# CCR2.net
KiCad netlist of a schematic drawn in EAGLE
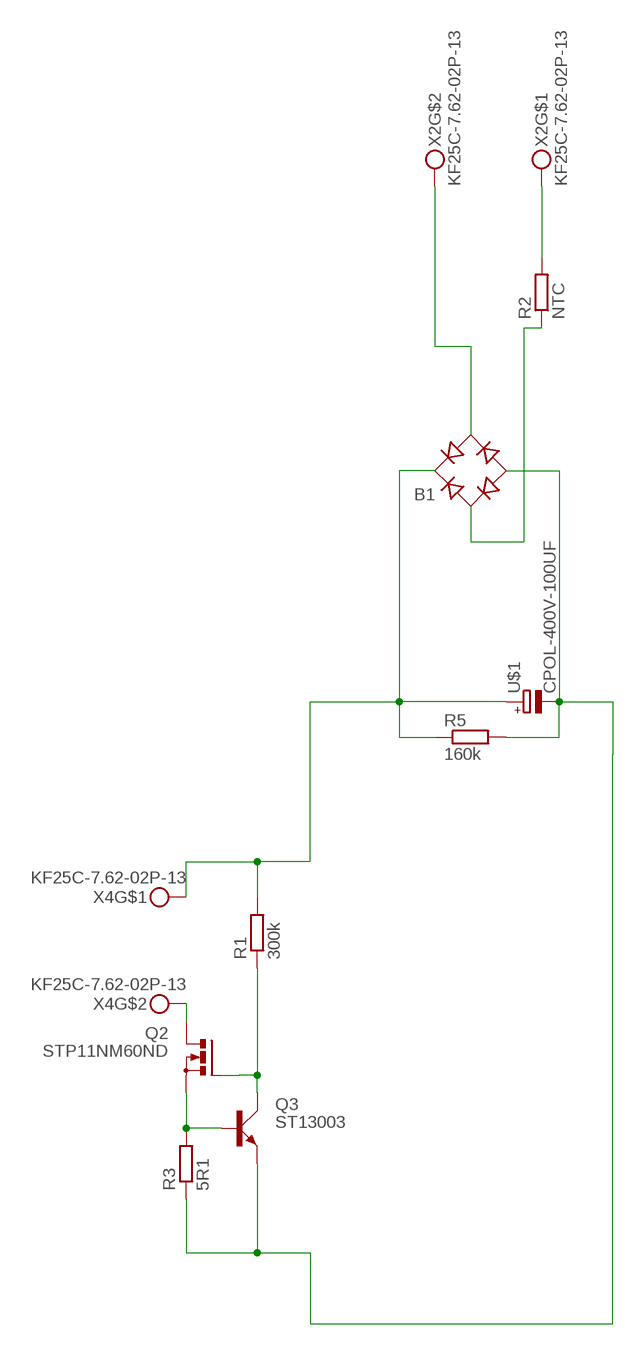
[diagram p0: schematic, sheet 1]

(export (version "E")
  (design (tool "Eeschema 10.0.6"))
  (components
    (comp (ref "B1")
      (value "RB1A")
      (footprint "eagle-import:RB1A")
      (libsource (lib "eagle-import") (part "RB1A"))
    )
    (comp (ref "Q2")
      (value "STP11NM60ND")
      (footprint "eagle-import:TO220BV")
      (libsource (lib "eagle-import") (part "BUZ11BV"))
    )
    (comp (ref "Q3")
      (value "ST13003")
      (footprint "eagle-import:SOT-92WIDE")
      (libsource (lib "eagle-import") (part "KSP42TA"))
    )
    (comp (ref "R1")
      (value "300k")
      (footprint "eagle-import:0411_12")
      (libsource (lib "eagle-import") (part "R-EU_0411/12"))
    )
    (comp (ref "R2")
      (value "NTC")
      (footprint "eagle-import:0309_10")
      (libsource (lib "eagle-import") (part "R-EU_0309/10"))
    )
    (comp (ref "R3")
      (value "5R1")
      (footprint "eagle-import:R0805")
      (libsource (lib "eagle-import") (part "R-EU_R0805"))
    )
    (comp (ref "R5")
      (value "160k")
      (footprint "eagle-import:0204_7")
      (libsource (lib "eagle-import") (part "R-EU_0204/7"))
    )
    (comp (ref "U$1")
      (value "CPOL-400V-100UF")
      (footprint "eagle-import:18_36.5_7.62")
      (libsource (lib "eagle-import") (part "CPOL-400V-100UF"))
    )
    (comp (ref "X2")
      (value "KF25C-7.62-02P-13")
      (footprint "eagle-import:KF25C-7.62-02P-13")
      (libsource (lib "eagle-import") (part "KF25C-7.62-02P-13"))
    )
    (comp (ref "X4")
      (value "KF25C-7.62-02P-13")
      (footprint "eagle-import:KF25C-7.62-02P-13")
      (libsource (lib "eagle-import") (part "KF25C-7.62-02P-13"))
    )
  )
  (nets
    (net (code "1") (name "Net-(B1-PadAC1)") (class "Default")
      (node (ref "B1") (pin "AC1") (pinfunction "AC1_AC1") (pintype "passive"))
      (node (ref "R2") (pin "1") (pinfunction "1_1") (pintype "passive"))
    )
    (net (code "2") (name "Net-(Q2-PadG)") (class "Default")
      (node (ref "Q2") (pin "G") (pinfunction "G_G") (pintype "passive"))
      (node (ref "Q3") (pin "C") (pinfunction "C_C") (pintype "passive"))
      (node (ref "R1") (pin "1") (pinfunction "1_1") (pintype "passive"))
    )
    (net (code "3") (name "Net-(Q2-PadS)") (class "Default")
      (node (ref "Q2") (pin "S") (pinfunction "S_S") (pintype "passive"))
      (node (ref "Q3") (pin "B") (pinfunction "B_B") (pintype "passive"))
      (node (ref "R3") (pin "2") (pinfunction "2_2") (pintype "passive"))
    )
    (net (code "4") (name "Net-(U$1-+)") (class "Default")
      (node (ref "B1") (pin "+") (pinfunction "+_+") (pintype "passive"))
      (node (ref "R1") (pin "2") (pinfunction "2_2") (pintype "passive"))
      (node (ref "R5") (pin "1") (pinfunction "1_1") (pintype "passive"))
      (node (ref "U$1") (pin "P$2") (pinfunction "+_P$2") (pintype "passive"))
      (node (ref "X4") (pin "P$1") (pinfunction "KL_P$1") (pintype "passive"))
    )
    (net (code "5") (name "Net-(U$1--)") (class "Default")
      (node (ref "B1") (pin "-") (pinfunction "-_-") (pintype "passive"))
      (node (ref "Q3") (pin "E") (pinfunction "E_E") (pintype "passive"))
      (node (ref "R3") (pin "1") (pinfunction "1_1") (pintype "passive"))
      (node (ref "R5") (pin "2") (pinfunction "2_2") (pintype "passive"))
      (node (ref "U$1") (pin "P$1") (pinfunction "-_P$1") (pintype "passive"))
    )
    (net (code "6") (name "Net-(X2A-KL)") (class "Default")
      (node (ref "R2") (pin "2") (pinfunction "2_2") (pintype "passive"))
      (node (ref "X2") (pin "P$1") (pinfunction "KL_P$1") (pintype "passive"))
    )
    (net (code "7") (name "Net-(X2B-KL)") (class "Default")
      (node (ref "B1") (pin "AC2") (pinfunction "AC2_AC2") (pintype "passive"))
      (node (ref "X2") (pin "P$2") (pinfunction "KL_P$2") (pintype "passive"))
    )
    (net (code "8") (name "Net-(X4B-KL)") (class "Default")
      (node (ref "Q2") (pin "D") (pinfunction "D_D") (pintype "passive"))
      (node (ref "X4") (pin "P$2") (pinfunction "KL_P$2") (pintype "passive"))
    )
  )
)
